# Main_Board.net
KiCad netlist of a schematic drawn in EAGLE
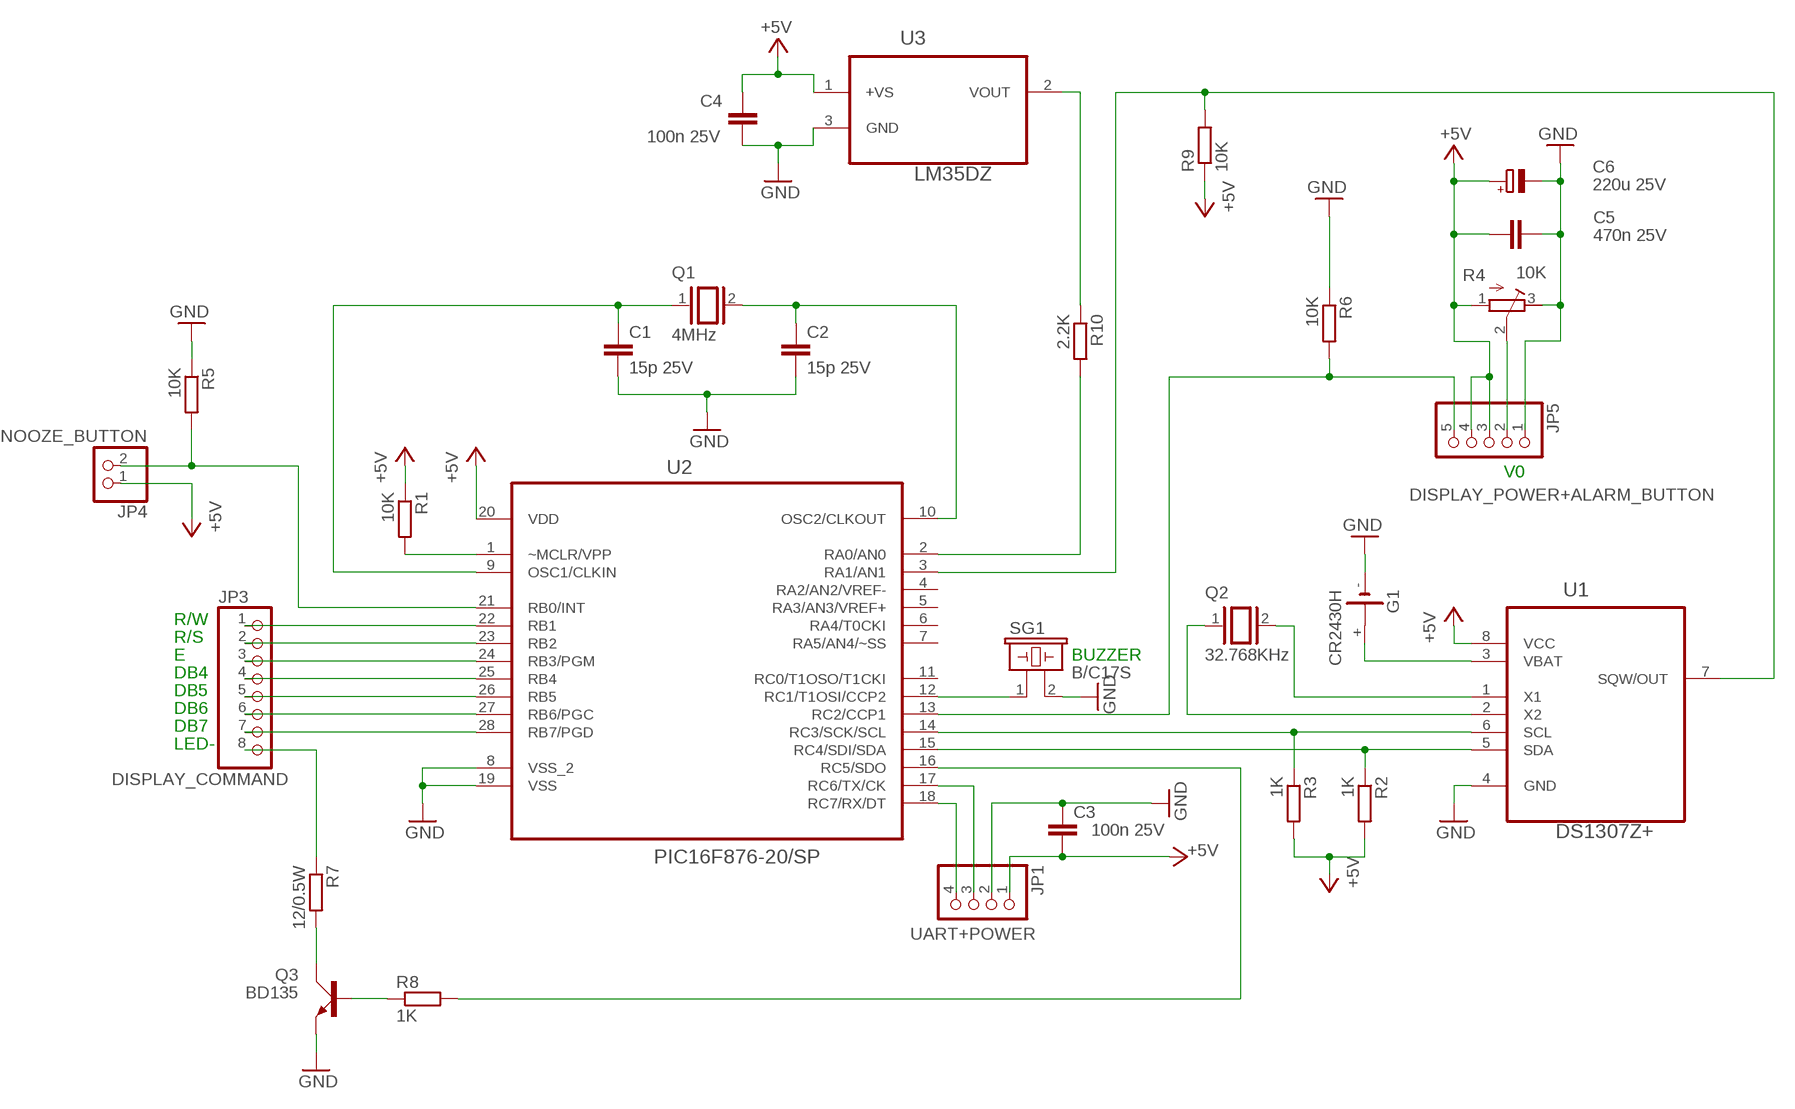
[diagram p0: schematic, sheet 1]

(export (version "E")
  (design (tool "Eeschema 10.0.6"))
  (components
    (comp (ref "C1")
      (value "15p 25V")
      (footprint "eagle-import:C2.5-3")
      (libsource (lib "eagle-import") (part "C2,5-3"))
    )
    (comp (ref "C2")
      (value "15p 25V")
      (footprint "eagle-import:C2.5-3")
      (libsource (lib "eagle-import") (part "C2,5-3"))
    )
    (comp (ref "C3")
      (value "100n 25V")
      (footprint "eagle-import:C5B3.5")
      (libsource (lib "eagle-import") (part "C5/3.5"))
    )
    (comp (ref "C4")
      (value "100n 25V")
      (footprint "eagle-import:C025-025X050")
      (libsource (lib "eagle-import") (part "C-EU025-025X050"))
    )
    (comp (ref "C5")
      (value "470n 25V")
      (footprint "eagle-import:C025-025X050")
      (libsource (lib "eagle-import") (part "C-EU025-025X050"))
    )
    (comp (ref "C6")
      (value "220u 25V")
      (footprint "eagle-import:E2,5-6")
      (libsource (lib "eagle-import") (part "CPOL-EUE2.5-6"))
    )
    (comp (ref "G1")
      (value "CR2430H")
      (footprint "eagle-import:CR2430H")
      (libsource (lib "eagle-import") (part "CR2430H"))
    )
    (comp (ref "JP1")
      (value "UART+POWER")
      (footprint "eagle-import:1X04")
      (libsource (lib "eagle-import") (part "PINHD-1X4"))
    )
    (comp (ref "JP3")
      (value "DISPLAY_COMMAND")
      (footprint "eagle-import:1X08")
      (libsource (lib "eagle-import") (part "PINHD-1X8"))
    )
    (comp (ref "JP4")
      (value "SNOOZE_BUTTON")
      (footprint "eagle-import:1X02")
      (libsource (lib "eagle-import") (part "PINHD-1X2"))
    )
    (comp (ref "JP5")
      (value "DISPLAY_POWER+ALARM_BUTTON")
      (footprint "eagle-import:1X05")
      (libsource (lib "eagle-import") (part "PINHD-1X5"))
    )
    (comp (ref "Q1")
      (value "4MHz")
      (footprint "eagle-import:QS")
      (libsource (lib "eagle-import") (part "XTAL/S"))
    )
    (comp (ref "Q2")
      (value "32.768KHz")
      (footprint "eagle-import:QS")
      (libsource (lib "eagle-import") (part "XTAL/S"))
    )
    (comp (ref "Q3")
      (value "BD135")
      (footprint "eagle-import:TO126AV")
      (libsource (lib "eagle-import") (part "BD139"))
    )
    (comp (ref "R1")
      (value "10K")
      (footprint "eagle-import:0207_12")
      (libsource (lib "eagle-import") (part "R-EU_0207/12"))
    )
    (comp (ref "R2")
      (value "1K")
      (footprint "eagle-import:0207_12")
      (libsource (lib "eagle-import") (part "R-EU_0207/12"))
    )
    (comp (ref "R3")
      (value "1K")
      (footprint "eagle-import:0207_12")
      (libsource (lib "eagle-import") (part "R-EU_0207/12"))
    )
    (comp (ref "R4")
      (value "10K")
      (footprint "eagle-import:RTRIM3339P")
      (libsource (lib "eagle-import") (part "R-TRIMM3339P"))
    )
    (comp (ref "R5")
      (value "10K")
      (footprint "eagle-import:0207_12")
      (libsource (lib "eagle-import") (part "R-EU_0207/12"))
    )
    (comp (ref "R6")
      (value "10K")
      (footprint "eagle-import:0207_12")
      (libsource (lib "eagle-import") (part "R-EU_0207/12"))
    )
    (comp (ref "R7")
      (value "12/0.5W")
      (footprint "eagle-import:0207_12")
      (libsource (lib "eagle-import") (part "R-EU_0207/12"))
    )
    (comp (ref "R8")
      (value "1K")
      (footprint "eagle-import:0207_12")
      (libsource (lib "eagle-import") (part "R-EU_0207/12"))
    )
    (comp (ref "R9")
      (value "10K")
      (footprint "eagle-import:0207_12")
      (libsource (lib "eagle-import") (part "R-EU_0207/12"))
    )
    (comp (ref "R10")
      (value "2.2K")
      (footprint "eagle-import:0207_12")
      (libsource (lib "eagle-import") (part "R-EU_0207/12"))
    )
    (comp (ref "SG1")
      (value "B/C17S")
      (footprint "eagle-import:B_C17S")
      (libsource (lib "eagle-import") (part "B/C17S"))
    )
    (comp (ref "U1")
      (value "DS1307Z+")
      (footprint "eagle-import:SOIC127P600X175-8N")
      (libsource (lib "eagle-import") (part "DS1307Z+"))
    )
    (comp (ref "U2")
      (value "PIC16F876-20/SP")
      (footprint "eagle-import:DIP254P762X406-28")
      (libsource (lib "eagle-import") (part "PIC16F876-20/SP"))
    )
    (comp (ref "U3")
      (value "LM35DZ")
      (footprint "eagle-import:TO127P254X495-3P")
      (libsource (lib "eagle-import") (part "LM35DZ"))
    )
  )
  (nets
    (net (code "1") (name "+5V") (class "Default")
      (node (ref "C3") (pin "2") (pinfunction "2_2") (pintype "passive"))
      (node (ref "C4") (pin "1") (pinfunction "1_1") (pintype "passive"))
      (node (ref "C5") (pin "1") (pinfunction "1_1") (pintype "passive"))
      (node (ref "C6") (pin "+") (pinfunction "+_+") (pintype "passive"))
      (node (ref "JP1") (pin "1") (pinfunction "1_1") (pintype "passive"))
      (node (ref "JP4") (pin "1") (pinfunction "1_1") (pintype "passive"))
      (node (ref "JP5") (pin "3") (pinfunction "3_3") (pintype "passive"))
      (node (ref "JP5") (pin "4") (pinfunction "4_4") (pintype "passive"))
      (node (ref "R1") (pin "1") (pinfunction "1_1") (pintype "passive"))
      (node (ref "R2") (pin "2") (pinfunction "2_2") (pintype "passive"))
      (node (ref "R3") (pin "2") (pinfunction "2_2") (pintype "passive"))
      (node (ref "R4") (pin "1") (pinfunction "A_1") (pintype "passive"))
      (node (ref "R9") (pin "1") (pinfunction "1_1") (pintype "passive"))
      (node (ref "U1") (pin "8") (pinfunction "VCC_8") (pintype "power_in"))
      (node (ref "U2") (pin "20") (pinfunction "VDD_20") (pintype "power_in"))
      (node (ref "U3") (pin "1") (pinfunction "+VS_1") (pintype "power_in"))
    )
    (net (code "2") (name "GND") (class "Default")
      (node (ref "C1") (pin "2") (pinfunction "2_2") (pintype "passive"))
      (node (ref "C2") (pin "2") (pinfunction "2_2") (pintype "passive"))
      (node (ref "C3") (pin "1") (pinfunction "1_1") (pintype "passive"))
      (node (ref "C4") (pin "2") (pinfunction "2_2") (pintype "passive"))
      (node (ref "C5") (pin "2") (pinfunction "2_2") (pintype "passive"))
      (node (ref "C6") (pin "-") (pinfunction "-_-") (pintype "passive"))
      (node (ref "G1") (pin "-") (pinfunction "-_-") (pintype "passive"))
      (node (ref "JP1") (pin "2") (pinfunction "2_2") (pintype "passive"))
      (node (ref "JP5") (pin "1") (pinfunction "1_1") (pintype "passive"))
      (node (ref "Q3") (pin "E") (pinfunction "E_E") (pintype "passive"))
      (node (ref "R4") (pin "3") (pinfunction "E_3") (pintype "passive"))
      (node (ref "R5") (pin "1") (pinfunction "1_1") (pintype "passive"))
      (node (ref "R6") (pin "1") (pinfunction "1_1") (pintype "passive"))
      (node (ref "SG1") (pin "2") (pinfunction "2_2") (pintype "passive"))
      (node (ref "U1") (pin "4") (pinfunction "GND_4") (pintype "passive"))
      (node (ref "U2") (pin "19") (pinfunction "VSS_19") (pintype "power_in"))
      (node (ref "U2") (pin "8") (pinfunction "VSS_2_8") (pintype "power_in"))
      (node (ref "U3") (pin "3") (pinfunction "GND_3") (pintype "passive"))
    )
    (net (code "3") (name "Net-(JP3-Pad8)") (class "Default")
      (node (ref "JP3") (pin "8") (pinfunction "8_8") (pintype "passive"))
      (node (ref "R7") (pin "1") (pinfunction "1_1") (pintype "passive"))
    )
    (net (code "4") (name "Net-(Q3-PadB)") (class "Default")
      (node (ref "Q3") (pin "B") (pinfunction "B_B") (pintype "passive"))
      (node (ref "R8") (pin "1") (pinfunction "1_1") (pintype "passive"))
    )
    (net (code "5") (name "Net-(Q3-PadC)") (class "Default")
      (node (ref "Q3") (pin "C") (pinfunction "C_C") (pintype "passive"))
      (node (ref "R7") (pin "2") (pinfunction "2_2") (pintype "passive"))
    )
    (net (code "6") (name "Net-(R4-S)") (class "Default")
      (node (ref "JP5") (pin "2") (pinfunction "2_2") (pintype "passive"))
      (node (ref "R4") (pin "2") (pinfunction "S_2") (pintype "passive"))
    )
    (net (code "7") (name "Net-(U1-SCL)") (class "Default")
      (node (ref "R3") (pin "1") (pinfunction "1_1") (pintype "passive"))
      (node (ref "U1") (pin "6") (pinfunction "SCL_6") (pintype "input"))
      (node (ref "U2") (pin "14") (pinfunction "RC3/SCK/SCL_14") (pintype "bidirectional"))
    )
    (net (code "8") (name "Net-(U1-SDA)") (class "Default")
      (node (ref "R2") (pin "1") (pinfunction "1_1") (pintype "passive"))
      (node (ref "U1") (pin "5") (pinfunction "SDA_5") (pintype "bidirectional"))
      (node (ref "U2") (pin "15") (pinfunction "RC4/SDI/SDA_15") (pintype "bidirectional"))
    )
    (net (code "9") (name "Net-(U1-SQW{slash}OUT)") (class "Default")
      (node (ref "R9") (pin "2") (pinfunction "2_2") (pintype "passive"))
      (node (ref "U1") (pin "7") (pinfunction "SQW/OUT_7") (pintype "output"))
      (node (ref "U2") (pin "3") (pinfunction "RA1/AN1_3") (pintype "bidirectional"))
    )
    (net (code "10") (name "Net-(U1-VBAT)") (class "Default")
      (node (ref "G1") (pin "+") (pinfunction "+_+") (pintype "passive"))
      (node (ref "U1") (pin "3") (pinfunction "VBAT_3") (pintype "input"))
    )
    (net (code "11") (name "Net-(U1-X1)") (class "Default")
      (node (ref "Q2") (pin "2") (pinfunction "2_2") (pintype "passive"))
      (node (ref "U1") (pin "1") (pinfunction "X1_1") (pintype "input"))
    )
    (net (code "12") (name "Net-(U1-X2)") (class "Default")
      (node (ref "Q2") (pin "1") (pinfunction "1_1") (pintype "passive"))
      (node (ref "U1") (pin "2") (pinfunction "X2_2") (pintype "input"))
    )
    (net (code "13") (name "Net-(U2-OSC1{slash}CLKIN)") (class "Default")
      (node (ref "C1") (pin "1") (pinfunction "1_1") (pintype "passive"))
      (node (ref "Q1") (pin "1") (pinfunction "1_1") (pintype "passive"))
      (node (ref "U2") (pin "9") (pinfunction "OSC1/CLKIN_9") (pintype "input"))
    )
    (net (code "14") (name "Net-(U2-OSC2{slash}CLKOUT)") (class "Default")
      (node (ref "C2") (pin "1") (pinfunction "1_1") (pintype "passive"))
      (node (ref "Q1") (pin "2") (pinfunction "2_2") (pintype "passive"))
      (node (ref "U2") (pin "10") (pinfunction "OSC2/CLKOUT_10") (pintype "output"))
    )
    (net (code "15") (name "Net-(U2-RA0{slash}AN0)") (class "Default")
      (node (ref "R10") (pin "2") (pinfunction "2_2") (pintype "passive"))
      (node (ref "U2") (pin "2") (pinfunction "RA0/AN0_2") (pintype "bidirectional"))
    )
    (net (code "16") (name "Net-(U2-RB0{slash}INT)") (class "Default")
      (node (ref "JP4") (pin "2") (pinfunction "2_2") (pintype "passive"))
      (node (ref "R5") (pin "2") (pinfunction "2_2") (pintype "passive"))
      (node (ref "U2") (pin "21") (pinfunction "RB0/INT_21") (pintype "bidirectional"))
    )
    (net (code "17") (name "Net-(U2-RB1)") (class "Default")
      (node (ref "JP3") (pin "1") (pinfunction "1_1") (pintype "passive"))
      (node (ref "U2") (pin "22") (pinfunction "RB1_22") (pintype "bidirectional"))
    )
    (net (code "18") (name "Net-(U2-RB2)") (class "Default")
      (node (ref "JP3") (pin "2") (pinfunction "2_2") (pintype "passive"))
      (node (ref "U2") (pin "23") (pinfunction "RB2_23") (pintype "bidirectional"))
    )
    (net (code "19") (name "Net-(U2-RB3{slash}PGM)") (class "Default")
      (node (ref "JP3") (pin "3") (pinfunction "3_3") (pintype "passive"))
      (node (ref "U2") (pin "24") (pinfunction "RB3/PGM_24") (pintype "bidirectional"))
    )
    (net (code "20") (name "Net-(U2-RB4)") (class "Default")
      (node (ref "JP3") (pin "4") (pinfunction "4_4") (pintype "passive"))
      (node (ref "U2") (pin "25") (pinfunction "RB4_25") (pintype "bidirectional"))
    )
    (net (code "21") (name "Net-(U2-RB5)") (class "Default")
      (node (ref "JP3") (pin "5") (pinfunction "5_5") (pintype "passive"))
      (node (ref "U2") (pin "26") (pinfunction "RB5_26") (pintype "bidirectional"))
    )
    (net (code "22") (name "Net-(U2-RB6{slash}PGC)") (class "Default")
      (node (ref "JP3") (pin "6") (pinfunction "6_6") (pintype "passive"))
      (node (ref "U2") (pin "27") (pinfunction "RB6/PGC_27") (pintype "bidirectional"))
    )
    (net (code "23") (name "Net-(U2-RB7{slash}PGD)") (class "Default")
      (node (ref "JP3") (pin "7") (pinfunction "7_7") (pintype "passive"))
      (node (ref "U2") (pin "28") (pinfunction "RB7/PGD_28") (pintype "bidirectional"))
    )
    (net (code "24") (name "Net-(U2-RC1{slash}T1OSI{slash}CCP2)") (class "Default")
      (node (ref "SG1") (pin "1") (pinfunction "1_1") (pintype "passive"))
      (node (ref "U2") (pin "12") (pinfunction "RC1/T1OSI/CCP2_12") (pintype "bidirectional"))
    )
    (net (code "25") (name "Net-(U2-RC2{slash}CCP1)") (class "Default")
      (node (ref "JP5") (pin "5") (pinfunction "5_5") (pintype "passive"))
      (node (ref "R6") (pin "2") (pinfunction "2_2") (pintype "passive"))
      (node (ref "U2") (pin "13") (pinfunction "RC2/CCP1_13") (pintype "bidirectional"))
    )
    (net (code "26") (name "Net-(U2-RC5{slash}SDO)") (class "Default")
      (node (ref "R8") (pin "2") (pinfunction "2_2") (pintype "passive"))
      (node (ref "U2") (pin "16") (pinfunction "RC5/SDO_16") (pintype "bidirectional"))
    )
    (net (code "27") (name "Net-(U2-RC6{slash}TX{slash}CK)") (class "Default")
      (node (ref "JP1") (pin "3") (pinfunction "3_3") (pintype "passive"))
      (node (ref "U2") (pin "17") (pinfunction "RC6/TX/CK_17") (pintype "bidirectional"))
    )
    (net (code "28") (name "Net-(U2-RC7{slash}RX{slash}DT)") (class "Default")
      (node (ref "JP1") (pin "4") (pinfunction "4_4") (pintype "passive"))
      (node (ref "U2") (pin "18") (pinfunction "RC7/RX/DT_18") (pintype "bidirectional"))
    )
    (net (code "29") (name "Net-(U2-~{MCLR{slash}VPP})") (class "Default")
      (node (ref "R1") (pin "2") (pinfunction "2_2") (pintype "passive"))
      (node (ref "U2") (pin "1") (pinfunction "~{MCLR/VPP}_1") (pintype "input"))
    )
    (net (code "30") (name "Net-(U3-VOUT)") (class "Default")
      (node (ref "R10") (pin "1") (pinfunction "1_1") (pintype "passive"))
      (node (ref "U3") (pin "2") (pinfunction "VOUT_2") (pintype "output"))
    )
    (net (code "31") (name "unconnected-(G1-+-Pad+@1)") (class "Default")
      (node (ref "G1") (pin "+@1") (pinfunction "+_+@1") (pintype "passive"))
    )
    (net (code "32") (name "unconnected-(U2-RA2{slash}AN2{slash}VREF--Pad4)") (class "Default")
      (node (ref "U2") (pin "4") (pinfunction "RA2/AN2/VREF-_4") (pintype "bidirectional"))
    )
    (net (code "33") (name "unconnected-(U2-RA3{slash}AN3{slash}VREF+-Pad5)") (class "Default")
      (node (ref "U2") (pin "5") (pinfunction "RA3/AN3/VREF+_5") (pintype "bidirectional"))
    )
    (net (code "34") (name "unconnected-(U2-RA4{slash}T0CKI-Pad6)") (class "Default")
      (node (ref "U2") (pin "6") (pinfunction "RA4/T0CKI_6") (pintype "bidirectional"))
    )
    (net (code "35") (name "unconnected-(U2-RA5{slash}AN4{slash}~{SS}-Pad7)") (class "Default")
      (node (ref "U2") (pin "7") (pinfunction "RA5/AN4/~{SS}_7") (pintype "bidirectional"))
    )
    (net (code "36") (name "unconnected-(U2-RC0{slash}T1OSO{slash}T1CKI-Pad11)") (class "Default")
      (node (ref "U2") (pin "11") (pinfunction "RC0/T1OSO/T1CKI_11") (pintype "bidirectional"))
    )
  )
)
